# InverterConnectors.net
KiCad netlist of a schematic drawn in Altium Designer
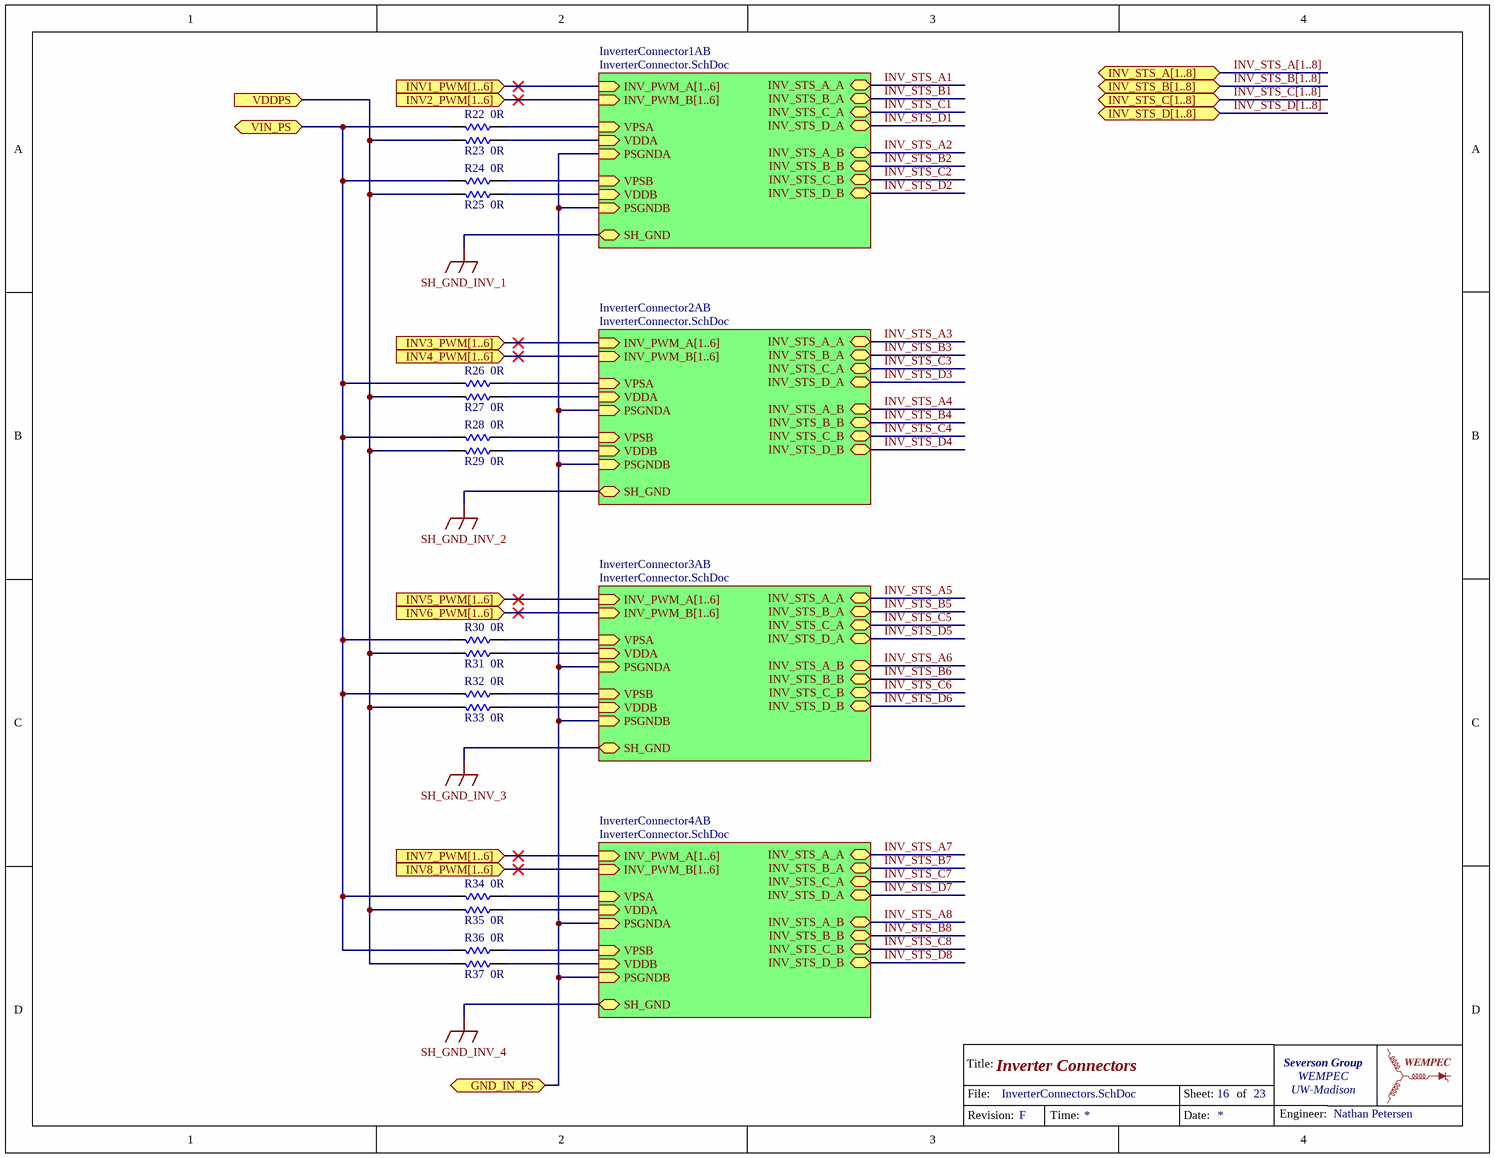
[diagram p0: InverterConnectors.SchDoc]

(export (version "E")
  (design (tool "Eeschema 10.0.6"))
  (components
    (comp (ref "R22")
      (value "0R")
      (footprint "1206-RES")
      (description "Resistor")
      (libsource (lib "AMDC") (part "Resistor"))
    )
    (comp (ref "R23")
      (value "0R")
      (footprint "1206-RES")
      (description "Resistor")
      (libsource (lib "AMDC") (part "Resistor"))
    )
    (comp (ref "R24")
      (value "0R")
      (footprint "1206-RES")
      (description "Resistor")
      (libsource (lib "AMDC") (part "Resistor"))
    )
    (comp (ref "R25")
      (value "0R")
      (footprint "1206-RES")
      (description "Resistor")
      (libsource (lib "AMDC") (part "Resistor"))
    )
    (comp (ref "R26")
      (value "0R")
      (footprint "1206-RES")
      (description "Resistor")
      (libsource (lib "AMDC") (part "Resistor"))
    )
    (comp (ref "R27")
      (value "0R")
      (footprint "1206-RES")
      (description "Resistor")
      (libsource (lib "AMDC") (part "Resistor"))
    )
    (comp (ref "R28")
      (value "0R")
      (footprint "1206-RES")
      (description "Resistor")
      (libsource (lib "AMDC") (part "Resistor"))
    )
    (comp (ref "R29")
      (value "0R")
      (footprint "1206-RES")
      (description "Resistor")
      (libsource (lib "AMDC") (part "Resistor"))
    )
    (comp (ref "R30")
      (value "0R")
      (footprint "1206-RES")
      (description "Resistor")
      (libsource (lib "AMDC") (part "Resistor"))
    )
    (comp (ref "R31")
      (value "0R")
      (footprint "1206-RES")
      (description "Resistor")
      (libsource (lib "AMDC") (part "Resistor"))
    )
    (comp (ref "R32")
      (value "0R")
      (footprint "1206-RES")
      (description "Resistor")
      (libsource (lib "AMDC") (part "Resistor"))
    )
    (comp (ref "R33")
      (value "0R")
      (footprint "1206-RES")
      (description "Resistor")
      (libsource (lib "AMDC") (part "Resistor"))
    )
    (comp (ref "R34")
      (value "0R")
      (footprint "1206-RES")
      (description "Resistor")
      (libsource (lib "AMDC") (part "Resistor"))
    )
    (comp (ref "R35")
      (value "0R")
      (footprint "1206-RES")
      (description "Resistor")
      (libsource (lib "AMDC") (part "Resistor"))
    )
    (comp (ref "R36")
      (value "0R")
      (footprint "1206-RES")
      (description "Resistor")
      (libsource (lib "AMDC") (part "Resistor"))
    )
    (comp (ref "R37")
      (value "0R")
      (footprint "1206-RES")
      (description "Resistor")
      (libsource (lib "AMDC") (part "Resistor"))
    )
  )
  (nets
    (net (code "94") (name "/VDDA") (class "Default")
      (node (ref "R27") (pin "1") (pinfunction "1_1") (pintype "passive"))
    )
    (net (code "95") (name "/VDDA_1") (class "Default")
      (node (ref "R23") (pin "1") (pinfunction "1_1") (pintype "passive"))
    )
    (net (code "96") (name "/VDDA_2") (class "Default")
      (node (ref "R31") (pin "1") (pinfunction "1_1") (pintype "passive"))
    )
    (net (code "97") (name "/VDDA_3") (class "Default")
      (node (ref "R35") (pin "1") (pinfunction "1_1") (pintype "passive"))
    )
    (net (code "98") (name "/VDDB") (class "Default")
      (node (ref "R37") (pin "1") (pinfunction "1_1") (pintype "passive"))
    )
    (net (code "99") (name "/VDDB_1") (class "Default")
      (node (ref "R25") (pin "1") (pinfunction "1_1") (pintype "passive"))
    )
    (net (code "100") (name "/VDDB_2") (class "Default")
      (node (ref "R29") (pin "1") (pinfunction "1_1") (pintype "passive"))
    )
    (net (code "101") (name "/VDDB_3") (class "Default")
      (node (ref "R33") (pin "1") (pinfunction "1_1") (pintype "passive"))
    )
    (net (code "102") (name "/VDDPS") (class "Default")
      (node (ref "R23") (pin "2") (pinfunction "2_2") (pintype "passive"))
      (node (ref "R25") (pin "2") (pinfunction "2_2") (pintype "passive"))
      (node (ref "R27") (pin "2") (pinfunction "2_2") (pintype "passive"))
      (node (ref "R29") (pin "2") (pinfunction "2_2") (pintype "passive"))
      (node (ref "R31") (pin "2") (pinfunction "2_2") (pintype "passive"))
      (node (ref "R33") (pin "2") (pinfunction "2_2") (pintype "passive"))
      (node (ref "R35") (pin "2") (pinfunction "2_2") (pintype "passive"))
      (node (ref "R37") (pin "2") (pinfunction "2_2") (pintype "passive"))
    )
    (net (code "103") (name "/VIN_PS") (class "Default")
      (node (ref "R22") (pin "2") (pinfunction "2_2") (pintype "passive"))
      (node (ref "R24") (pin "2") (pinfunction "2_2") (pintype "passive"))
      (node (ref "R26") (pin "2") (pinfunction "2_2") (pintype "passive"))
      (node (ref "R28") (pin "2") (pinfunction "2_2") (pintype "passive"))
      (node (ref "R30") (pin "2") (pinfunction "2_2") (pintype "passive"))
      (node (ref "R32") (pin "2") (pinfunction "2_2") (pintype "passive"))
      (node (ref "R34") (pin "2") (pinfunction "2_2") (pintype "passive"))
      (node (ref "R36") (pin "2") (pinfunction "2_2") (pintype "passive"))
    )
    (net (code "104") (name "/VPSA") (class "Default")
      (node (ref "R26") (pin "1") (pinfunction "1_1") (pintype "passive"))
    )
    (net (code "105") (name "/VPSA_1") (class "Default")
      (node (ref "R22") (pin "1") (pinfunction "1_1") (pintype "passive"))
    )
    (net (code "106") (name "/VPSA_2") (class "Default")
      (node (ref "R30") (pin "1") (pinfunction "1_1") (pintype "passive"))
    )
    (net (code "107") (name "/VPSA_3") (class "Default")
      (node (ref "R34") (pin "1") (pinfunction "1_1") (pintype "passive"))
    )
    (net (code "108") (name "/VPSB") (class "Default")
      (node (ref "R28") (pin "1") (pinfunction "1_1") (pintype "passive"))
    )
    (net (code "109") (name "/VPSB_1") (class "Default")
      (node (ref "R24") (pin "1") (pinfunction "1_1") (pintype "passive"))
    )
    (net (code "110") (name "/VPSB_2") (class "Default")
      (node (ref "R32") (pin "1") (pinfunction "1_1") (pintype "passive"))
    )
    (net (code "111") (name "/VPSB_3") (class "Default")
      (node (ref "R36") (pin "1") (pinfunction "1_1") (pintype "passive"))
    )
  )
)
